# openSX70_LENS_BELLOWS_V50_20180120.net
KiCad netlist of a schematic drawn in EAGLE
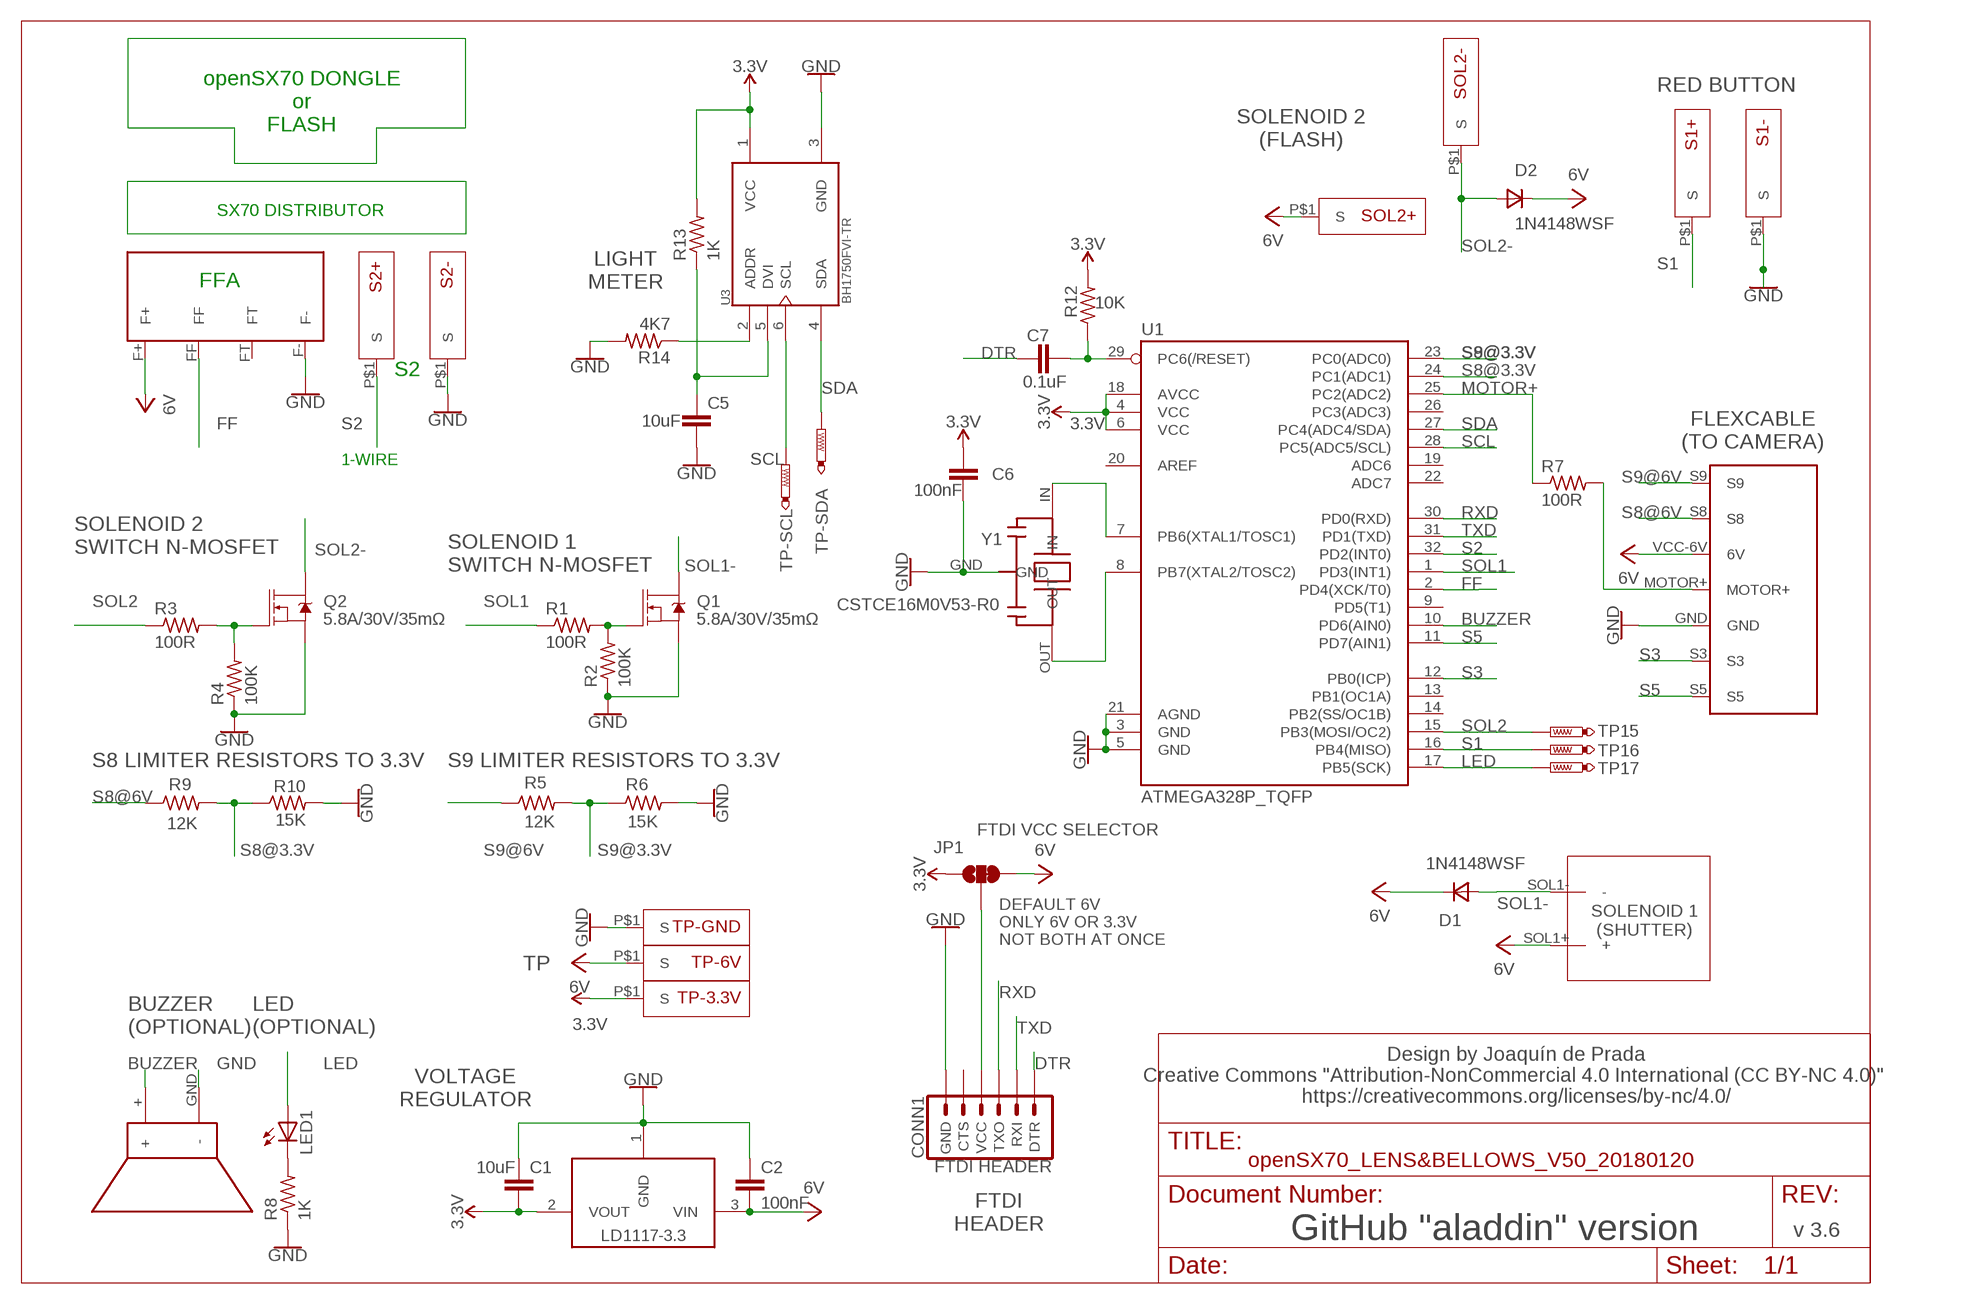
[diagram p0: schematic, sheet 1]

(export (version "E")
  (design (tool "Eeschema 10.0.6"))
  (components
    (comp (ref "BUZZ1")
      (value "CSET8-5G")
      (footprint "eagle-import:CSET8-5G_PACKAGE")
      (libsource (lib "eagle-import") (part "CSET8-5G"))
    )
    (comp (ref "C1")
      (value "10uF")
      (footprint "eagle-import:0603")
      (libsource (lib "eagle-import") (part "10UF-0603-6.3V-20%"))
    )
    (comp (ref "C2")
      (value "100nF")
      (footprint "eagle-import:C0603K")
      (libsource (lib "eagle-import") (part "C-EUC0603K"))
    )
    (comp (ref "C5")
      (value "10uF")
      (footprint "eagle-import:0603")
      (libsource (lib "eagle-import") (part "10UF-0603-6.3V-20%"))
    )
    (comp (ref "C6")
      (value "100nF")
      (footprint "eagle-import:C0603K")
      (libsource (lib "eagle-import") (part "C-EUC0603K"))
    )
    (comp (ref "C7")
      (value "0.1uF")
      (footprint "eagle-import:0603")
      (libsource (lib "eagle-import") (part "0.1UF-0603-25V-(+80/-20%)"))
    )
    (comp (ref "CONN1")
      (value "FTDI HEADER")
      (footprint "eagle-import:1X06")
      (libsource (lib "eagle-import") (part "6_PIN_SERIAL_TARGET"))
    )
    (comp (ref "D1")
      (value "1N4148WSF")
      (footprint "eagle-import:SOD323")
      (fields (field (name "MPN") "CDSOD323-T05C"))
      (libsource (lib "eagle-import") (part "DSOD323"))
    )
    (comp (ref "D2")
      (value "1N4148WSF")
      (footprint "eagle-import:SOD323")
      (fields (field (name "MPN") "CDSOD323-T05C"))
      (libsource (lib "eagle-import") (part "DSOD323"))
    )
    (comp (ref "JP1")
      (value "FTDI VCC SELECTOR")
      (footprint "eagle-import:SMT-JUMPER_3_1-NC_TRACE_SILK")
      (libsource (lib "eagle-import") (part "JUMPER-SMT_3_1-NC_TRACE_SILK"))
    )
    (comp (ref "LD11173.3V")
      (value "LD1117 3.3V")
      (footprint "eagle-import:SOT223")
      (fields (field (name "MF") "Advanced Monolithic Systems") (field (name "MP") "AMS1117-5.0"))
      (libsource (lib "eagle-import") (part "LD1117-3.3"))
    )
    (comp (ref "LED1")
      (value "LEDCHIPLED_0805")
      (footprint "eagle-import:CHIPLED_0805")
      (libsource (lib "eagle-import") (part "LEDCHIPLED_0805"))
    )
    (comp (ref "Q1")
      (value "5.8A/30V/35mΩ")
      (footprint "eagle-import:SOT23-3")
      (libsource (lib "eagle-import") (part "MOSFET-NCH-AO3404A"))
    )
    (comp (ref "Q2")
      (value "5.8A/30V/35mΩ")
      (footprint "eagle-import:SOT23-3")
      (libsource (lib "eagle-import") (part "MOSFET-NCH-AO3404A"))
    )
    (comp (ref "R1")
      (value "100R")
      (footprint "eagle-import:R0603")
      (libsource (lib "eagle-import") (part "R-US_R0603"))
    )
    (comp (ref "R2")
      (value "100K")
      (footprint "eagle-import:R0603")
      (libsource (lib "eagle-import") (part "R-US_R0603"))
    )
    (comp (ref "R3")
      (value "100R")
      (footprint "eagle-import:R0603")
      (libsource (lib "eagle-import") (part "R-US_R0603"))
    )
    (comp (ref "R4")
      (value "100K")
      (footprint "eagle-import:R0603")
      (libsource (lib "eagle-import") (part "R-US_R0603"))
    )
    (comp (ref "R5")
      (value "12K")
      (footprint "eagle-import:R0603")
      (libsource (lib "eagle-import") (part "R-US_R0603"))
    )
    (comp (ref "R6")
      (value "15K")
      (footprint "eagle-import:R0603")
      (libsource (lib "eagle-import") (part "R-US_R0603"))
    )
    (comp (ref "R7")
      (value "100R")
      (footprint "eagle-import:R0603")
      (libsource (lib "eagle-import") (part "R-US_R0603"))
    )
    (comp (ref "R8")
      (value "1K")
      (footprint "eagle-import:R0603")
      (libsource (lib "eagle-import") (part "R-US_R0603"))
    )
    (comp (ref "R9")
      (value "12K")
      (footprint "eagle-import:R0603")
      (libsource (lib "eagle-import") (part "R-US_R0603"))
    )
    (comp (ref "R10")
      (value "15K")
      (footprint "eagle-import:R0603")
      (libsource (lib "eagle-import") (part "R-US_R0603"))
    )
    (comp (ref "R12")
      (value "10K")
      (footprint "eagle-import:R0603")
      (libsource (lib "eagle-import") (part "R-US_R0603"))
    )
    (comp (ref "R13")
      (value "1K")
      (footprint "eagle-import:R0603")
      (libsource (lib "eagle-import") (part "R-US_R0603"))
    )
    (comp (ref "R14")
      (value "4K7")
      (footprint "eagle-import:R0603")
      (libsource (lib "eagle-import") (part "R-US_R0603"))
    )
    (comp (ref "S1+")
      (value "SX70-S-PAD-NEW")
      (footprint "eagle-import:SX70-S-PAD2")
      (libsource (lib "eagle-import") (part "SX70-S-PAD-NEW"))
    )
    (comp (ref "S1-")
      (value "SX70-S-PAD-NEW")
      (footprint "eagle-import:SX70-S-PAD2")
      (libsource (lib "eagle-import") (part "SX70-S-PAD-NEW"))
    )
    (comp (ref "S2+")
      (value "SX70-S-PAD-NEW")
      (footprint "eagle-import:SX70-S-PAD2")
      (libsource (lib "eagle-import") (part "SX70-S-PAD-NEW"))
    )
    (comp (ref "S2-")
      (value "SX70-S-PAD-NEW")
      (footprint "eagle-import:SX70-S-PAD2")
      (libsource (lib "eagle-import") (part "SX70-S-PAD-NEW"))
    )
    (comp (ref "SOL1")
      (value "SX70-SOLENOID1-2PADS")
      (footprint "eagle-import:SX70-SOLENOID1-2")
      (libsource (lib "eagle-import") (part "SX70-SOLENOID1-2PADS"))
    )
    (comp (ref "SOL2+")
      (value "SX70-S-PAD-NEW")
      (footprint "eagle-import:SX70-S-PAD2")
      (libsource (lib "eagle-import") (part "SX70-S-PAD-NEW"))
    )
    (comp (ref "SOL2-")
      (value "SX70-S-PAD-NEW")
      (footprint "eagle-import:SX70-S-PAD2")
      (libsource (lib "eagle-import") (part "SX70-S-PAD-NEW"))
    )
    (comp (ref "TP-3.3V")
      (value "SX70-S-PAD-NEW")
      (footprint "eagle-import:SX70-S-PAD2")
      (libsource (lib "eagle-import") (part "SX70-S-PAD-NEW"))
    )
    (comp (ref "TP-6V")
      (value "SX70-S-PAD-NEW")
      (footprint "eagle-import:SX70-S-PAD2")
      (libsource (lib "eagle-import") (part "SX70-S-PAD-NEW"))
    )
    (comp (ref "TP-GND")
      (value "SX70-S-PAD-NEW")
      (footprint "eagle-import:SX70-S-PAD2")
      (libsource (lib "eagle-import") (part "SX70-S-PAD-NEW"))
    )
    (comp (ref "TP-SCL")
      (value "PTR1TP08R")
      (footprint "eagle-import:TP08R")
      (libsource (lib "eagle-import") (part "PTR1TP08R"))
    )
    (comp (ref "TP-SDA")
      (value "PTR1TP08R")
      (footprint "eagle-import:TP08R")
      (libsource (lib "eagle-import") (part "PTR1TP08R"))
    )
    (comp (ref "TP15")
      (value "PTR1TP08R")
      (footprint "eagle-import:TP08R")
      (libsource (lib "eagle-import") (part "PTR1TP08R"))
    )
    (comp (ref "TP16")
      (value "PTR1TP08R")
      (footprint "eagle-import:TP08R")
      (libsource (lib "eagle-import") (part "PTR1TP08R"))
    )
    (comp (ref "TP17")
      (value "PTR1TP08R")
      (footprint "eagle-import:TP08R")
      (libsource (lib "eagle-import") (part "PTR1TP08R"))
    )
    (comp (ref "U$1")
      (value "SX70-7-PAD")
      (footprint "eagle-import:SX70-7-PAD")
      (libsource (lib "eagle-import") (part "SX70-7-PAD"))
    )
    (comp (ref "U$2")
      (value "FFA")
      (footprint "eagle-import:FFA-PAD-PACKAGE")
      (libsource (lib "eagle-import") (part "SX70-FFA-PAD"))
    )
    (comp (ref "U1")
      (value "ATMEGA328P_TQFP")
      (footprint "eagle-import:TQFP32-08")
      (libsource (lib "eagle-import") (part "ATMEGA328P_TQFP"))
    )
    (comp (ref "U3")
      (value "BH1750FVI-TR")
      (footprint "eagle-import:SOTFL50P300X75-6N")
      (fields (field (name "MF") "Rohm"))
      (libsource (lib "eagle-import") (part "BH1750FVI-TR"))
    )
    (comp (ref "Y1")
      (value "CSTCE16M0V53-R0")
      (footprint "eagle-import:CFP95P160X100-3N")
      (fields (field (name "MF") "Murata"))
      (libsource (lib "eagle-import") (part "CSTCE16M0V53-R0"))
    )
  )
  (nets
    (net (code "1") (name "/BUZZER") (class "Default")
      (node (ref "BUZZ1") (pin "+") (pinfunction "+_+") (pintype "bidirectional"))
      (node (ref "U1") (pin "10") (pinfunction "PD6(AIN0)_10") (pintype "bidirectional"))
    )
    (net (code "2") (name "/DTR") (class "Default")
      (node (ref "C7") (pin "1") (pinfunction "1_1") (pintype "passive"))
      (node (ref "CONN1") (pin "1") (pinfunction "DTR_1") (pintype "passive"))
    )
    (net (code "3") (name "/FF") (class "Default")
      (node (ref "U$2") (pin "FF") (pinfunction "FF_FF") (pintype "bidirectional"))
      (node (ref "U1") (pin "2") (pinfunction "PD4(XCK/T0)_2") (pintype "bidirectional"))
    )
    (net (code "4") (name "/LED") (class "Default")
      (node (ref "LED1") (pin "A") (pinfunction "A_A") (pintype "passive"))
      (node (ref "TP17") (pin "TP") (pinfunction "TP_TP") (pintype "input"))
      (node (ref "U1") (pin "17") (pinfunction "PB5(SCK)_17") (pintype "bidirectional"))
    )
    (net (code "5") (name "/MOTOR+") (class "Default")
      (node (ref "R7") (pin "1") (pinfunction "1_1") (pintype "passive"))
      (node (ref "U1") (pin "25") (pinfunction "PC2(ADC2)_25") (pintype "bidirectional"))
    )
    (net (code "6") (name "/RXD") (class "Default")
      (node (ref "CONN1") (pin "3") (pinfunction "TXO_3") (pintype "passive"))
      (node (ref "U1") (pin "30") (pinfunction "PD0(RXD)_30") (pintype "bidirectional"))
    )
    (net (code "7") (name "/S1") (class "Default")
      (node (ref "S1+") (pin "P$1") (pinfunction "S_P$1") (pintype "bidirectional"))
      (node (ref "TP16") (pin "TP") (pinfunction "TP_TP") (pintype "input"))
      (node (ref "U1") (pin "16") (pinfunction "PB4(MISO)_16") (pintype "bidirectional"))
    )
    (net (code "8") (name "/S2") (class "Default")
      (node (ref "S2+") (pin "P$1") (pinfunction "S_P$1") (pintype "bidirectional"))
      (node (ref "U1") (pin "32") (pinfunction "PD2(INT0)_32") (pintype "bidirectional"))
    )
    (net (code "9") (name "/S3") (class "Default")
      (node (ref "U$1") (pin "S3") (pinfunction "S3_S3") (pintype "bidirectional"))
      (node (ref "U1") (pin "12") (pinfunction "PB0(ICP)_12") (pintype "bidirectional"))
    )
    (net (code "10") (name "/S5") (class "Default")
      (node (ref "U$1") (pin "S5") (pinfunction "S5_S5") (pintype "bidirectional"))
      (node (ref "U1") (pin "11") (pinfunction "PD7(AIN1)_11") (pintype "bidirectional"))
    )
    (net (code "11") (name "/S8@3.3V") (class "Default")
      (node (ref "R10") (pin "1") (pinfunction "1_1") (pintype "passive"))
      (node (ref "R9") (pin "2") (pinfunction "2_2") (pintype "passive"))
      (node (ref "U1") (pin "24") (pinfunction "PC1(ADC1)_24") (pintype "bidirectional"))
    )
    (net (code "12") (name "/S8@6V") (class "Default")
      (node (ref "R9") (pin "1") (pinfunction "1_1") (pintype "passive"))
      (node (ref "U$1") (pin "S8") (pinfunction "S8_S8") (pintype "bidirectional"))
    )
    (net (code "13") (name "/S9@3.3V") (class "Default")
      (node (ref "R5") (pin "2") (pinfunction "2_2") (pintype "passive"))
      (node (ref "R6") (pin "1") (pinfunction "1_1") (pintype "passive"))
      (node (ref "U1") (pin "23") (pinfunction "PC0(ADC0)_23") (pintype "bidirectional"))
    )
    (net (code "14") (name "/S9@6V") (class "Default")
      (node (ref "R5") (pin "1") (pinfunction "1_1") (pintype "passive"))
      (node (ref "U$1") (pin "S9") (pinfunction "S9_S9") (pintype "bidirectional"))
    )
    (net (code "15") (name "/SCL") (class "Default")
      (node (ref "TP-SCL") (pin "TP") (pinfunction "TP_TP") (pintype "input"))
      (node (ref "U1") (pin "28") (pinfunction "PC5(ADC5/SCL)_28") (pintype "bidirectional"))
      (node (ref "U3") (pin "6") (pinfunction "SCL_6") (pintype "input"))
    )
    (net (code "16") (name "/SDA") (class "Default")
      (node (ref "TP-SDA") (pin "TP") (pinfunction "TP_TP") (pintype "input"))
      (node (ref "U1") (pin "27") (pinfunction "PC4(ADC4/SDA)_27") (pintype "bidirectional"))
      (node (ref "U3") (pin "4") (pinfunction "SDA_4") (pintype "bidirectional"))
    )
    (net (code "17") (name "/SOL1") (class "Default")
      (node (ref "R1") (pin "1") (pinfunction "1_1") (pintype "passive"))
      (node (ref "U1") (pin "1") (pinfunction "PD3(INT1)_1") (pintype "bidirectional"))
    )
    (net (code "18") (name "/SOL1-") (class "Default")
      (node (ref "D1") (pin "2") (pinfunction "A_2") (pintype "passive"))
      (node (ref "Q1") (pin "3") (pinfunction "D_3") (pintype "bidirectional"))
      (node (ref "SOL1") (pin "SOL1-") (pinfunction "-_SOL1-") (pintype "bidirectional"))
    )
    (net (code "19") (name "/SOL2") (class "Default")
      (node (ref "R3") (pin "1") (pinfunction "1_1") (pintype "passive"))
      (node (ref "TP15") (pin "TP") (pinfunction "TP_TP") (pintype "input"))
      (node (ref "U1") (pin "15") (pinfunction "PB3(MOSI/OC2)_15") (pintype "bidirectional"))
    )
    (net (code "20") (name "/SOL2-") (class "Default")
      (node (ref "D2") (pin "2") (pinfunction "A_2") (pintype "passive"))
      (node (ref "Q2") (pin "3") (pinfunction "D_3") (pintype "bidirectional"))
      (node (ref "SOL2-") (pin "P$1") (pinfunction "S_P$1") (pintype "bidirectional"))
    )
    (net (code "21") (name "/TXD") (class "Default")
      (node (ref "CONN1") (pin "2") (pinfunction "RXI_2") (pintype "passive"))
      (node (ref "U1") (pin "31") (pinfunction "PD1(TXD)_31") (pintype "bidirectional"))
    )
    (net (code "22") (name "3.3V") (class "Default")
      (node (ref "C1") (pin "2") (pinfunction "2_2") (pintype "passive"))
      (node (ref "C6") (pin "1") (pinfunction "1_1") (pintype "passive"))
      (node (ref "JP1") (pin "1") (pinfunction "1_1") (pintype "passive"))
      (node (ref "LD11173.3V") (pin "2") (pinfunction "VOUT_2") (pintype "bidirectional"))
      (node (ref "R12") (pin "2") (pinfunction "2_2") (pintype "passive"))
      (node (ref "R13") (pin "2") (pinfunction "2_2") (pintype "passive"))
      (node (ref "TP-3.3V") (pin "P$1") (pinfunction "S_P$1") (pintype "bidirectional"))
      (node (ref "U1") (pin "18") (pinfunction "AVCC_18") (pintype "bidirectional"))
      (node (ref "U1") (pin "4") (pinfunction "VCC_4") (pintype "bidirectional"))
      (node (ref "U1") (pin "6") (pinfunction "VCC_6") (pintype "bidirectional"))
      (node (ref "U3") (pin "1") (pinfunction "VCC_1") (pintype "power_in"))
    )
    (net (code "23") (name "6V") (class "Default")
      (node (ref "C2") (pin "2") (pinfunction "2_2") (pintype "passive"))
      (node (ref "D1") (pin "1") (pinfunction "C_1") (pintype "passive"))
      (node (ref "D2") (pin "1") (pinfunction "C_1") (pintype "passive"))
      (node (ref "JP1") (pin "3") (pinfunction "3_3") (pintype "passive"))
      (node (ref "LD11173.3V") (pin "3") (pinfunction "VIN_3") (pintype "bidirectional"))
      (node (ref "SOL1") (pin "SOL1+") (pinfunction "+_SOL1+") (pintype "bidirectional"))
      (node (ref "SOL2+") (pin "P$1") (pinfunction "S_P$1") (pintype "bidirectional"))
      (node (ref "TP-6V") (pin "P$1") (pinfunction "S_P$1") (pintype "bidirectional"))
      (node (ref "U$1") (pin "VCC-6V") (pinfunction "6V_VCC-6V") (pintype "bidirectional"))
      (node (ref "U$2") (pin "F+") (pinfunction "F+_F+") (pintype "bidirectional"))
    )
    (net (code "24") (name "GND") (class "Default")
      (node (ref "BUZZ1") (pin "GND") (pinfunction "-_GND") (pintype "bidirectional"))
      (node (ref "C1") (pin "1") (pinfunction "1_1") (pintype "passive"))
      (node (ref "C2") (pin "1") (pinfunction "1_1") (pintype "passive"))
      (node (ref "C5") (pin "2") (pinfunction "2_2") (pintype "passive"))
      (node (ref "C6") (pin "2") (pinfunction "2_2") (pintype "passive"))
      (node (ref "CONN1") (pin "6") (pinfunction "GND_6") (pintype "passive"))
      (node (ref "LD11173.3V") (pin "1") (pinfunction "GND_1") (pintype "bidirectional"))
      (node (ref "Q1") (pin "2") (pinfunction "S_2") (pintype "bidirectional"))
      (node (ref "Q2") (pin "2") (pinfunction "S_2") (pintype "bidirectional"))
      (node (ref "R10") (pin "2") (pinfunction "2_2") (pintype "passive"))
      (node (ref "R14") (pin "2") (pinfunction "2_2") (pintype "passive"))
      (node (ref "R2") (pin "1") (pinfunction "1_1") (pintype "passive"))
      (node (ref "R4") (pin "1") (pinfunction "1_1") (pintype "passive"))
      (node (ref "R6") (pin "2") (pinfunction "2_2") (pintype "passive"))
      (node (ref "R8") (pin "1") (pinfunction "1_1") (pintype "passive"))
      (node (ref "S1-") (pin "P$1") (pinfunction "S_P$1") (pintype "bidirectional"))
      (node (ref "S2-") (pin "P$1") (pinfunction "S_P$1") (pintype "bidirectional"))
      (node (ref "TP-GND") (pin "P$1") (pinfunction "S_P$1") (pintype "bidirectional"))
      (node (ref "U$1") (pin "GND") (pinfunction "GND_GND") (pintype "bidirectional"))
      (node (ref "U$2") (pin "F-") (pinfunction "F-_F-") (pintype "bidirectional"))
      (node (ref "U1") (pin "21") (pinfunction "AGND_21") (pintype "bidirectional"))
      (node (ref "U1") (pin "3") (pinfunction "GND_3") (pintype "bidirectional"))
      (node (ref "U1") (pin "5") (pinfunction "GND_5") (pintype "bidirectional"))
      (node (ref "U3") (pin "3") (pinfunction "GND_3") (pintype "power_in"))
      (node (ref "Y1") (pin "GND") (pinfunction "GND_GND") (pintype "passive"))
    )
    (net (code "25") (name "Net-(CONN1-VCC)") (class "Default")
      (node (ref "CONN1") (pin "4") (pinfunction "VCC_4") (pintype "passive"))
      (node (ref "JP1") (pin "2") (pinfunction "2_2") (pintype "passive"))
    )
    (net (code "26") (name "Net-(LED1-PadC)") (class "Default")
      (node (ref "LED1") (pin "C") (pinfunction "C_C") (pintype "passive"))
      (node (ref "R8") (pin "2") (pinfunction "2_2") (pintype "passive"))
    )
    (net (code "27") (name "Net-(Q1-G)") (class "Default")
      (node (ref "Q1") (pin "1") (pinfunction "G_1") (pintype "bidirectional"))
      (node (ref "R1") (pin "2") (pinfunction "2_2") (pintype "passive"))
      (node (ref "R2") (pin "2") (pinfunction "2_2") (pintype "passive"))
    )
    (net (code "28") (name "Net-(Q2-G)") (class "Default")
      (node (ref "Q2") (pin "1") (pinfunction "G_1") (pintype "bidirectional"))
      (node (ref "R3") (pin "2") (pinfunction "2_2") (pintype "passive"))
      (node (ref "R4") (pin "2") (pinfunction "2_2") (pintype "passive"))
    )
    (net (code "29") (name "Net-(R7-Pad2)") (class "Default")
      (node (ref "R7") (pin "2") (pinfunction "2_2") (pintype "passive"))
      (node (ref "U$1") (pin "MOTOR+") (pinfunction "MOTOR+_MOTOR+") (pintype "bidirectional"))
    )
    (net (code "30") (name "Net-(U1-PB6(XTAL1{slash}TOSC1))") (class "Default")
      (node (ref "U1") (pin "7") (pinfunction "PB6(XTAL1/TOSC1)_7") (pintype "bidirectional"))
      (node (ref "Y1") (pin "IN") (pinfunction "IN_IN") (pintype "input"))
    )
    (net (code "31") (name "Net-(U1-PB7(XTAL2{slash}TOSC2))") (class "Default")
      (node (ref "U1") (pin "8") (pinfunction "PB7(XTAL2/TOSC2)_8") (pintype "bidirectional"))
      (node (ref "Y1") (pin "OUT") (pinfunction "OUT_OUT") (pintype "output"))
    )
    (net (code "32") (name "Net-(U1-PC6({slash}RESET))") (class "Default")
      (node (ref "C7") (pin "2") (pinfunction "2_2") (pintype "passive"))
      (node (ref "R12") (pin "1") (pinfunction "1_1") (pintype "passive"))
      (node (ref "U1") (pin "29") (pinfunction "PC6(/RESET)_29") (pintype "bidirectional"))
    )
    (net (code "33") (name "Net-(U3-ADDR)") (class "Default")
      (node (ref "R14") (pin "1") (pinfunction "1_1") (pintype "passive"))
      (node (ref "U3") (pin "2") (pinfunction "ADDR_2") (pintype "input"))
    )
    (net (code "34") (name "Net-(U3-DVI)") (class "Default")
      (node (ref "C5") (pin "1") (pinfunction "1_1") (pintype "passive"))
      (node (ref "R13") (pin "1") (pinfunction "1_1") (pintype "passive"))
      (node (ref "U3") (pin "5") (pinfunction "DVI_5") (pintype "input"))
    )
    (net (code "35") (name "unconnected-(CONN1-CTS-Pad5)") (class "Default")
      (node (ref "CONN1") (pin "5") (pinfunction "CTS_5") (pintype "passive"))
    )
    (net (code "36") (name "unconnected-(U$2-PadFT)") (class "Default")
      (node (ref "U$2") (pin "FT") (pinfunction "FT_FT") (pintype "bidirectional"))
    )
    (net (code "37") (name "unconnected-(U1-ADC6-Pad19)") (class "Default")
      (node (ref "U1") (pin "19") (pinfunction "ADC6_19") (pintype "bidirectional"))
    )
    (net (code "38") (name "unconnected-(U1-ADC7-Pad22)") (class "Default")
      (node (ref "U1") (pin "22") (pinfunction "ADC7_22") (pintype "bidirectional"))
    )
    (net (code "39") (name "unconnected-(U1-AREF-Pad20)") (class "Default")
      (node (ref "U1") (pin "20") (pinfunction "AREF_20") (pintype "bidirectional"))
    )
    (net (code "40") (name "unconnected-(U1-PB1(OC1A)-Pad13)") (class "Default")
      (node (ref "U1") (pin "13") (pinfunction "PB1(OC1A)_13") (pintype "bidirectional"))
    )
    (net (code "41") (name "unconnected-(U1-PB2(SS{slash}OC1B)-Pad14)") (class "Default")
      (node (ref "U1") (pin "14") (pinfunction "PB2(SS/OC1B)_14") (pintype "bidirectional"))
    )
    (net (code "42") (name "unconnected-(U1-PC3(ADC3)-Pad26)") (class "Default")
      (node (ref "U1") (pin "26") (pinfunction "PC3(ADC3)_26") (pintype "bidirectional"))
    )
    (net (code "43") (name "unconnected-(U1-PD5(T1)-Pad9)") (class "Default")
      (node (ref "U1") (pin "9") (pinfunction "PD5(T1)_9") (pintype "bidirectional"))
    )
  )
)
